# rotary-launcher.net
KiCad netlist of a schematic drawn in EAGLE
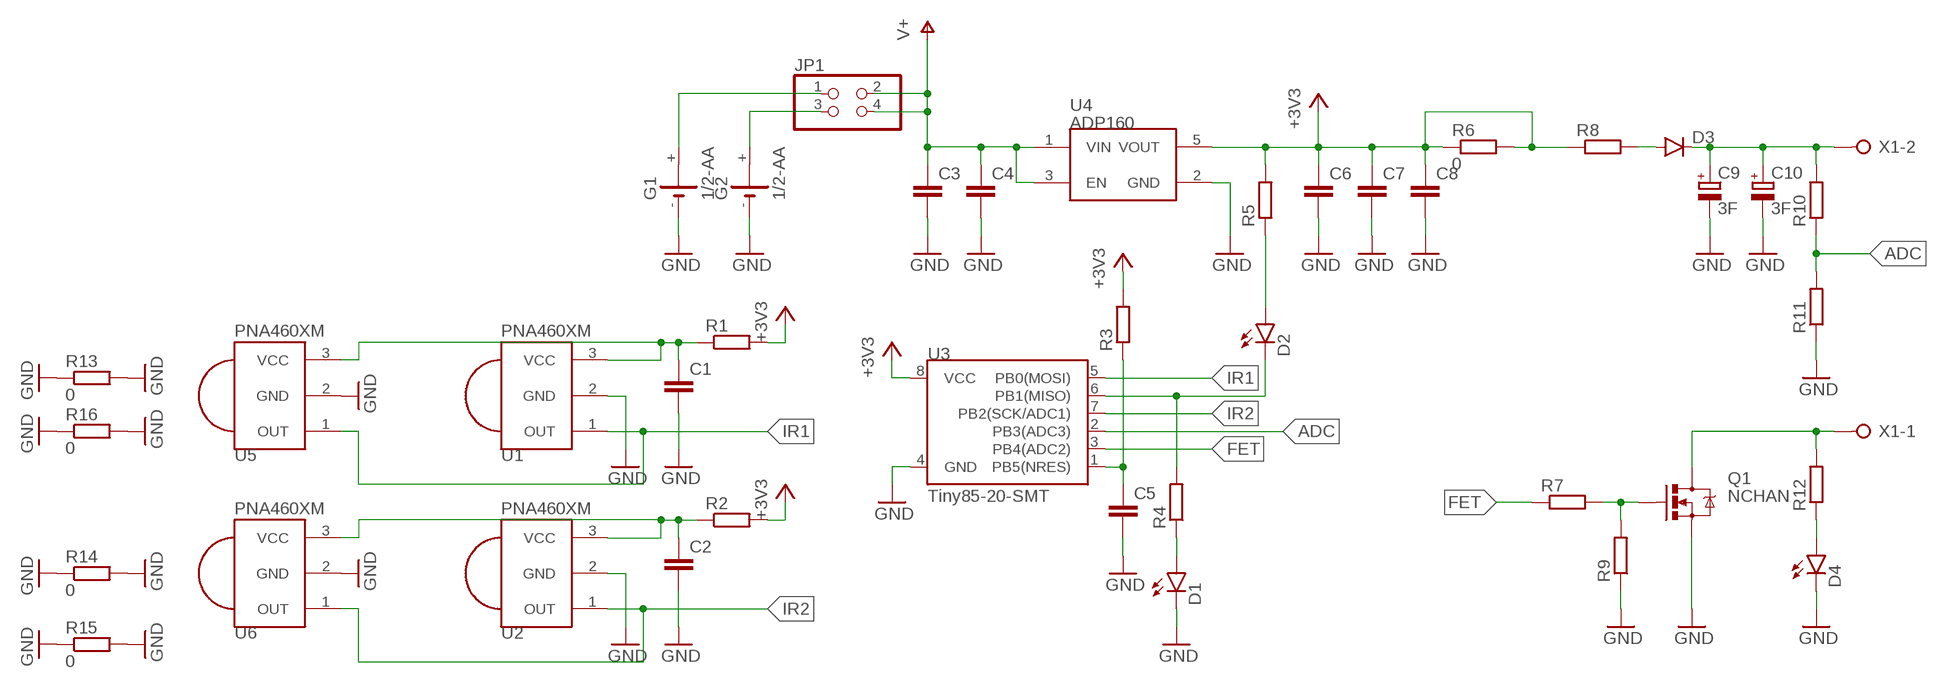
[diagram p0: schematic, sheet 1]

(export (version "E")
  (design (tool "Eeschema 10.0.6"))
  (components
    (comp (ref "C1")
      (value "C-EUC0805")
      (footprint "eagle-import:C0805")
      (libsource (lib "eagle-import") (part "C-EUC0805"))
    )
    (comp (ref "C2")
      (value "C-EUC0805")
      (footprint "eagle-import:C0805")
      (libsource (lib "eagle-import") (part "C-EUC0805"))
    )
    (comp (ref "C3")
      (value "C-EUC0805")
      (footprint "eagle-import:C0805")
      (libsource (lib "eagle-import") (part "C-EUC0805"))
    )
    (comp (ref "C4")
      (value "C-EUC0805")
      (footprint "eagle-import:C0805")
      (libsource (lib "eagle-import") (part "C-EUC0805"))
    )
    (comp (ref "C5")
      (value "C-EUC0805")
      (footprint "eagle-import:C0805")
      (libsource (lib "eagle-import") (part "C-EUC0805"))
    )
    (comp (ref "C6")
      (value "C-EUC0805")
      (footprint "eagle-import:C0805")
      (libsource (lib "eagle-import") (part "C-EUC0805"))
    )
    (comp (ref "C7")
      (value "C-EUC0805")
      (footprint "eagle-import:C0805")
      (libsource (lib "eagle-import") (part "C-EUC0805"))
    )
    (comp (ref "C8")
      (value "C-EUC0805")
      (footprint "eagle-import:C0805")
      (libsource (lib "eagle-import") (part "C-EUC0805"))
    )
    (comp (ref "C9")
      (value "3F")
      (footprint "eagle-import:E3,5-8-HOR")
      (libsource (lib "eagle-import") (part "SUPERCAPH"))
    )
    (comp (ref "C10")
      (value "3F")
      (footprint "eagle-import:E3,5-8-HOR")
      (libsource (lib "eagle-import") (part "SUPERCAPH"))
    )
    (comp (ref "D1")
      (value "LED0603")
      (footprint "eagle-import:LED-0603")
      (libsource (lib "eagle-import") (part "LED0603"))
    )
    (comp (ref "D2")
      (value "LED0603")
      (footprint "eagle-import:LED-0603")
      (libsource (lib "eagle-import") (part "LED0603"))
    )
    (comp (ref "D3")
      (value "DIODESMB")
      (footprint "eagle-import:SMB-DIODE")
      (libsource (lib "eagle-import") (part "DIODESMB"))
    )
    (comp (ref "D4")
      (value "LED0603")
      (footprint "eagle-import:LED-0603")
      (libsource (lib "eagle-import") (part "LED0603"))
    )
    (comp (ref "G1")
      (value "1/2-AA")
      (footprint "eagle-import:CRAA")
      (libsource (lib "eagle-import") (part "CR-AA"))
    )
    (comp (ref "G2")
      (value "1/2-AA")
      (footprint "eagle-import:CRAA")
      (libsource (lib "eagle-import") (part "CR-AA"))
    )
    (comp (ref "JP1")
      (value "PINHD-2X2")
      (footprint "eagle-import:2X02")
      (libsource (lib "eagle-import") (part "PINHD-2X2"))
    )
    (comp (ref "Q1")
      (value "NCHAN")
      (footprint "eagle-import:SOT23-3")
      (libsource (lib "eagle-import") (part "MOSFET-NCHANNELAO3404A"))
    )
    (comp (ref "R1")
      (value "R-EU_R0603")
      (footprint "eagle-import:R0603")
      (libsource (lib "eagle-import") (part "R-EU_R0603"))
    )
    (comp (ref "R2")
      (value "R-EU_R0603")
      (footprint "eagle-import:R0603")
      (libsource (lib "eagle-import") (part "R-EU_R0603"))
    )
    (comp (ref "R3")
      (value "R-EU_R0603")
      (footprint "eagle-import:R0603")
      (libsource (lib "eagle-import") (part "R-EU_R0603"))
    )
    (comp (ref "R4")
      (value "R-EU_R0603")
      (footprint "eagle-import:R0603")
      (libsource (lib "eagle-import") (part "R-EU_R0603"))
    )
    (comp (ref "R5")
      (value "R-EU_R0603")
      (footprint "eagle-import:R0603")
      (libsource (lib "eagle-import") (part "R-EU_R0603"))
    )
    (comp (ref "R6")
      (value "0")
      (footprint "eagle-import:R1206")
      (libsource (lib "eagle-import") (part "R-EU_R1206"))
    )
    (comp (ref "R7")
      (value "R-EU_R0603")
      (footprint "eagle-import:R0603")
      (libsource (lib "eagle-import") (part "R-EU_R0603"))
    )
    (comp (ref "R8")
      (value "R-EU_R1206")
      (footprint "eagle-import:R1206")
      (libsource (lib "eagle-import") (part "R-EU_R1206"))
    )
    (comp (ref "R9")
      (value "R-EU_R0603")
      (footprint "eagle-import:R0603")
      (libsource (lib "eagle-import") (part "R-EU_R0603"))
    )
    (comp (ref "R10")
      (value "R-EU_R0603")
      (footprint "eagle-import:R0603")
      (libsource (lib "eagle-import") (part "R-EU_R0603"))
    )
    (comp (ref "R11")
      (value "R-EU_R0603")
      (footprint "eagle-import:R0603")
      (libsource (lib "eagle-import") (part "R-EU_R0603"))
    )
    (comp (ref "R12")
      (value "R-EU_R0603")
      (footprint "eagle-import:R0603")
      (libsource (lib "eagle-import") (part "R-EU_R0603"))
    )
    (comp (ref "R13")
      (value "0")
      (footprint "eagle-import:R1206")
      (libsource (lib "eagle-import") (part "R-EU_R1206"))
    )
    (comp (ref "R14")
      (value "0")
      (footprint "eagle-import:R1206")
      (libsource (lib "eagle-import") (part "R-EU_R1206"))
    )
    (comp (ref "R15")
      (value "0")
      (footprint "eagle-import:R1206")
      (libsource (lib "eagle-import") (part "R-EU_R1206"))
    )
    (comp (ref "R16")
      (value "0")
      (footprint "eagle-import:R1206")
      (libsource (lib "eagle-import") (part "R-EU_R1206"))
    )
    (comp (ref "U1")
      (value "PNA460XM")
      (footprint "eagle-import:PNA460XM")
      (libsource (lib "eagle-import") (part "PNA460XM"))
    )
    (comp (ref "U2")
      (value "PNA460XM")
      (footprint "eagle-import:PNA460XM")
      (libsource (lib "eagle-import") (part "PNA460XM"))
    )
    (comp (ref "U3")
      (value "Tiny85-20-SMT")
      (footprint "eagle-import:SO08-EIAJ")
      (libsource (lib "eagle-import") (part "ATTINY45TINY85-20-SMT"))
    )
    (comp (ref "U4")
      (value "ADP160")
      (footprint "eagle-import:SOT23-5")
      (libsource (lib "eagle-import") (part "ADP160"))
    )
    (comp (ref "U5")
      (value "PNA460XM")
      (footprint "eagle-import:PNA460XM")
      (libsource (lib "eagle-import") (part "PNA460XM"))
    )
    (comp (ref "U6")
      (value "PNA460XM")
      (footprint "eagle-import:PNA460XM")
      (libsource (lib "eagle-import") (part "PNA460XM"))
    )
    (comp (ref "X1")
      (value "W237-02P")
      (footprint "eagle-import:W237-132")
      (libsource (lib "eagle-import") (part "W237-02P"))
    )
  )
  (nets
    (net (code "1") (name "+3V3") (class "Default")
      (node (ref "C6") (pin "1") (pinfunction "1_1") (pintype "passive"))
      (node (ref "C7") (pin "1") (pinfunction "1_1") (pintype "passive"))
      (node (ref "C8") (pin "1") (pinfunction "1_1") (pintype "passive"))
      (node (ref "R1") (pin "2") (pinfunction "2_2") (pintype "passive"))
      (node (ref "R2") (pin "2") (pinfunction "2_2") (pintype "passive"))
      (node (ref "R3") (pin "2") (pinfunction "2_2") (pintype "passive"))
      (node (ref "R5") (pin "2") (pinfunction "2_2") (pintype "passive"))
      (node (ref "R6") (pin "1") (pinfunction "1_1") (pintype "passive"))
      (node (ref "R6") (pin "2") (pinfunction "2_2") (pintype "passive"))
      (node (ref "R8") (pin "1") (pinfunction "1_1") (pintype "passive"))
      (node (ref "U3") (pin "8") (pinfunction "VCC_8") (pintype "bidirectional"))
      (node (ref "U4") (pin "5") (pinfunction "VOUT_5") (pintype "bidirectional"))
    )
    (net (code "2") (name "ADC") (class "Default")
      (node (ref "R10") (pin "1") (pinfunction "1_1") (pintype "passive"))
      (node (ref "R11") (pin "2") (pinfunction "2_2") (pintype "passive"))
      (node (ref "U3") (pin "2") (pinfunction "PB3(ADC3)_2") (pintype "bidirectional"))
    )
    (net (code "3") (name "FET") (class "Default")
      (node (ref "R7") (pin "1") (pinfunction "1_1") (pintype "passive"))
      (node (ref "U3") (pin "3") (pinfunction "PB4(ADC2)_3") (pintype "bidirectional"))
    )
    (net (code "4") (name "GND") (class "Default")
      (node (ref "C1") (pin "2") (pinfunction "2_2") (pintype "passive"))
      (node (ref "C10") (pin "-") (pinfunction "-_-") (pintype "passive"))
      (node (ref "C2") (pin "2") (pinfunction "2_2") (pintype "passive"))
      (node (ref "C3") (pin "2") (pinfunction "2_2") (pintype "passive"))
      (node (ref "C4") (pin "2") (pinfunction "2_2") (pintype "passive"))
      (node (ref "C5") (pin "2") (pinfunction "2_2") (pintype "passive"))
      (node (ref "C6") (pin "2") (pinfunction "2_2") (pintype "passive"))
      (node (ref "C7") (pin "2") (pinfunction "2_2") (pintype "passive"))
      (node (ref "C8") (pin "2") (pinfunction "2_2") (pintype "passive"))
      (node (ref "C9") (pin "-") (pinfunction "-_-") (pintype "passive"))
      (node (ref "D1") (pin "C") (pinfunction "C_C") (pintype "passive"))
      (node (ref "D4") (pin "C") (pinfunction "C_C") (pintype "passive"))
      (node (ref "G1") (pin "-") (pinfunction "-_-") (pintype "passive"))
      (node (ref "G2") (pin "-") (pinfunction "-_-") (pintype "passive"))
      (node (ref "Q1") (pin "2") (pinfunction "S_2") (pintype "passive"))
      (node (ref "R11") (pin "1") (pinfunction "1_1") (pintype "passive"))
      (node (ref "R13") (pin "1") (pinfunction "1_1") (pintype "passive"))
      (node (ref "R13") (pin "2") (pinfunction "2_2") (pintype "passive"))
      (node (ref "R14") (pin "1") (pinfunction "1_1") (pintype "passive"))
      (node (ref "R14") (pin "2") (pinfunction "2_2") (pintype "passive"))
      (node (ref "R15") (pin "1") (pinfunction "1_1") (pintype "passive"))
      (node (ref "R15") (pin "2") (pinfunction "2_2") (pintype "passive"))
      (node (ref "R16") (pin "1") (pinfunction "1_1") (pintype "passive"))
      (node (ref "R16") (pin "2") (pinfunction "2_2") (pintype "passive"))
      (node (ref "R9") (pin "1") (pinfunction "1_1") (pintype "passive"))
      (node (ref "U1") (pin "2") (pinfunction "GND_2") (pintype "power_in"))
      (node (ref "U2") (pin "2") (pinfunction "GND_2") (pintype "power_in"))
      (node (ref "U3") (pin "4") (pinfunction "GND_4") (pintype "bidirectional"))
      (node (ref "U4") (pin "2") (pinfunction "GND_2") (pintype "bidirectional"))
      (node (ref "U5") (pin "2") (pinfunction "GND_2") (pintype "power_in"))
      (node (ref "U6") (pin "2") (pinfunction "GND_2") (pintype "power_in"))
    )
    (net (code "5") (name "IR1") (class "Default")
      (node (ref "U1") (pin "1") (pinfunction "OUT_1") (pintype "output"))
      (node (ref "U3") (pin "5") (pinfunction "PB0(MOSI)_5") (pintype "bidirectional"))
      (node (ref "U5") (pin "1") (pinfunction "OUT_1") (pintype "output"))
    )
    (net (code "6") (name "IR2") (class "Default")
      (node (ref "U2") (pin "1") (pinfunction "OUT_1") (pintype "output"))
      (node (ref "U3") (pin "7") (pinfunction "PB2(SCK/ADC1)_7") (pintype "bidirectional"))
      (node (ref "U6") (pin "1") (pinfunction "OUT_1") (pintype "output"))
    )
    (net (code "7") (name "Net-(D1-PadA)") (class "Default")
      (node (ref "D1") (pin "A") (pinfunction "A_A") (pintype "passive"))
      (node (ref "R4") (pin "1") (pinfunction "1_1") (pintype "passive"))
    )
    (net (code "8") (name "Net-(D2-PadA)") (class "Default")
      (node (ref "D2") (pin "A") (pinfunction "A_A") (pintype "passive"))
      (node (ref "R5") (pin "1") (pinfunction "1_1") (pintype "passive"))
    )
    (net (code "9") (name "Net-(D3-PadA)") (class "Default")
      (node (ref "D3") (pin "A") (pinfunction "A_A") (pintype "passive"))
      (node (ref "R8") (pin "2") (pinfunction "2_2") (pintype "passive"))
    )
    (net (code "10") (name "Net-(D4-PadA)") (class "Default")
      (node (ref "D4") (pin "A") (pinfunction "A_A") (pintype "passive"))
      (node (ref "R12") (pin "1") (pinfunction "1_1") (pintype "passive"))
    )
    (net (code "11") (name "Net-(G1-Pad+)") (class "Default")
      (node (ref "G1") (pin "+") (pinfunction "+_+") (pintype "passive"))
      (node (ref "JP1") (pin "1") (pinfunction "1_1") (pintype "passive"))
    )
    (net (code "12") (name "Net-(G2-Pad+)") (class "Default")
      (node (ref "G2") (pin "+") (pinfunction "+_+") (pintype "passive"))
      (node (ref "JP1") (pin "3") (pinfunction "3_3") (pintype "passive"))
    )
    (net (code "13") (name "Net-(Q1-D)") (class "Default")
      (node (ref "Q1") (pin "3") (pinfunction "D_3") (pintype "passive"))
      (node (ref "R12") (pin "2") (pinfunction "2_2") (pintype "passive"))
      (node (ref "X1") (pin "1") (pinfunction "KL_1") (pintype "passive"))
    )
    (net (code "14") (name "Net-(Q1-G)") (class "Default")
      (node (ref "Q1") (pin "1") (pinfunction "G_1") (pintype "passive"))
      (node (ref "R7") (pin "2") (pinfunction "2_2") (pintype "passive"))
      (node (ref "R9") (pin "2") (pinfunction "2_2") (pintype "passive"))
    )
    (net (code "15") (name "Net-(U1-VCC)") (class "Default")
      (node (ref "C1") (pin "1") (pinfunction "1_1") (pintype "passive"))
      (node (ref "R1") (pin "1") (pinfunction "1_1") (pintype "passive"))
      (node (ref "U1") (pin "3") (pinfunction "VCC_3") (pintype "power_in"))
      (node (ref "U5") (pin "3") (pinfunction "VCC_3") (pintype "power_in"))
    )
    (net (code "16") (name "Net-(U2-VCC)") (class "Default")
      (node (ref "C2") (pin "1") (pinfunction "1_1") (pintype "passive"))
      (node (ref "R2") (pin "1") (pinfunction "1_1") (pintype "passive"))
      (node (ref "U2") (pin "3") (pinfunction "VCC_3") (pintype "power_in"))
      (node (ref "U6") (pin "3") (pinfunction "VCC_3") (pintype "power_in"))
    )
    (net (code "17") (name "Net-(U3-PB1(MISO))") (class "Default")
      (node (ref "D2") (pin "C") (pinfunction "C_C") (pintype "passive"))
      (node (ref "R4") (pin "2") (pinfunction "2_2") (pintype "passive"))
      (node (ref "U3") (pin "6") (pinfunction "PB1(MISO)_6") (pintype "bidirectional"))
    )
    (net (code "18") (name "Net-(U3-PB5(NRES))") (class "Default")
      (node (ref "C5") (pin "1") (pinfunction "1_1") (pintype "passive"))
      (node (ref "R3") (pin "1") (pinfunction "1_1") (pintype "passive"))
      (node (ref "U3") (pin "1") (pinfunction "PB5(NRES)_1") (pintype "bidirectional"))
    )
    (net (code "19") (name "Net-(X1B-KL)") (class "Default")
      (node (ref "C10") (pin "+") (pinfunction "+_+") (pintype "passive"))
      (node (ref "C9") (pin "+") (pinfunction "+_+") (pintype "passive"))
      (node (ref "D3") (pin "C") (pinfunction "C_C") (pintype "passive"))
      (node (ref "R10") (pin "2") (pinfunction "2_2") (pintype "passive"))
      (node (ref "X1") (pin "2") (pinfunction "KL_2") (pintype "passive"))
    )
    (net (code "20") (name "V+") (class "Default")
      (node (ref "C3") (pin "1") (pinfunction "1_1") (pintype "passive"))
      (node (ref "C4") (pin "1") (pinfunction "1_1") (pintype "passive"))
      (node (ref "JP1") (pin "2") (pinfunction "2_2") (pintype "passive"))
      (node (ref "JP1") (pin "4") (pinfunction "4_4") (pintype "passive"))
      (node (ref "U4") (pin "1") (pinfunction "VIN_1") (pintype "bidirectional"))
      (node (ref "U4") (pin "3") (pinfunction "EN_3") (pintype "bidirectional"))
    )
  )
)
